# STM32G4_V1.net
KiCad netlist of a schematic drawn in Altium Designer
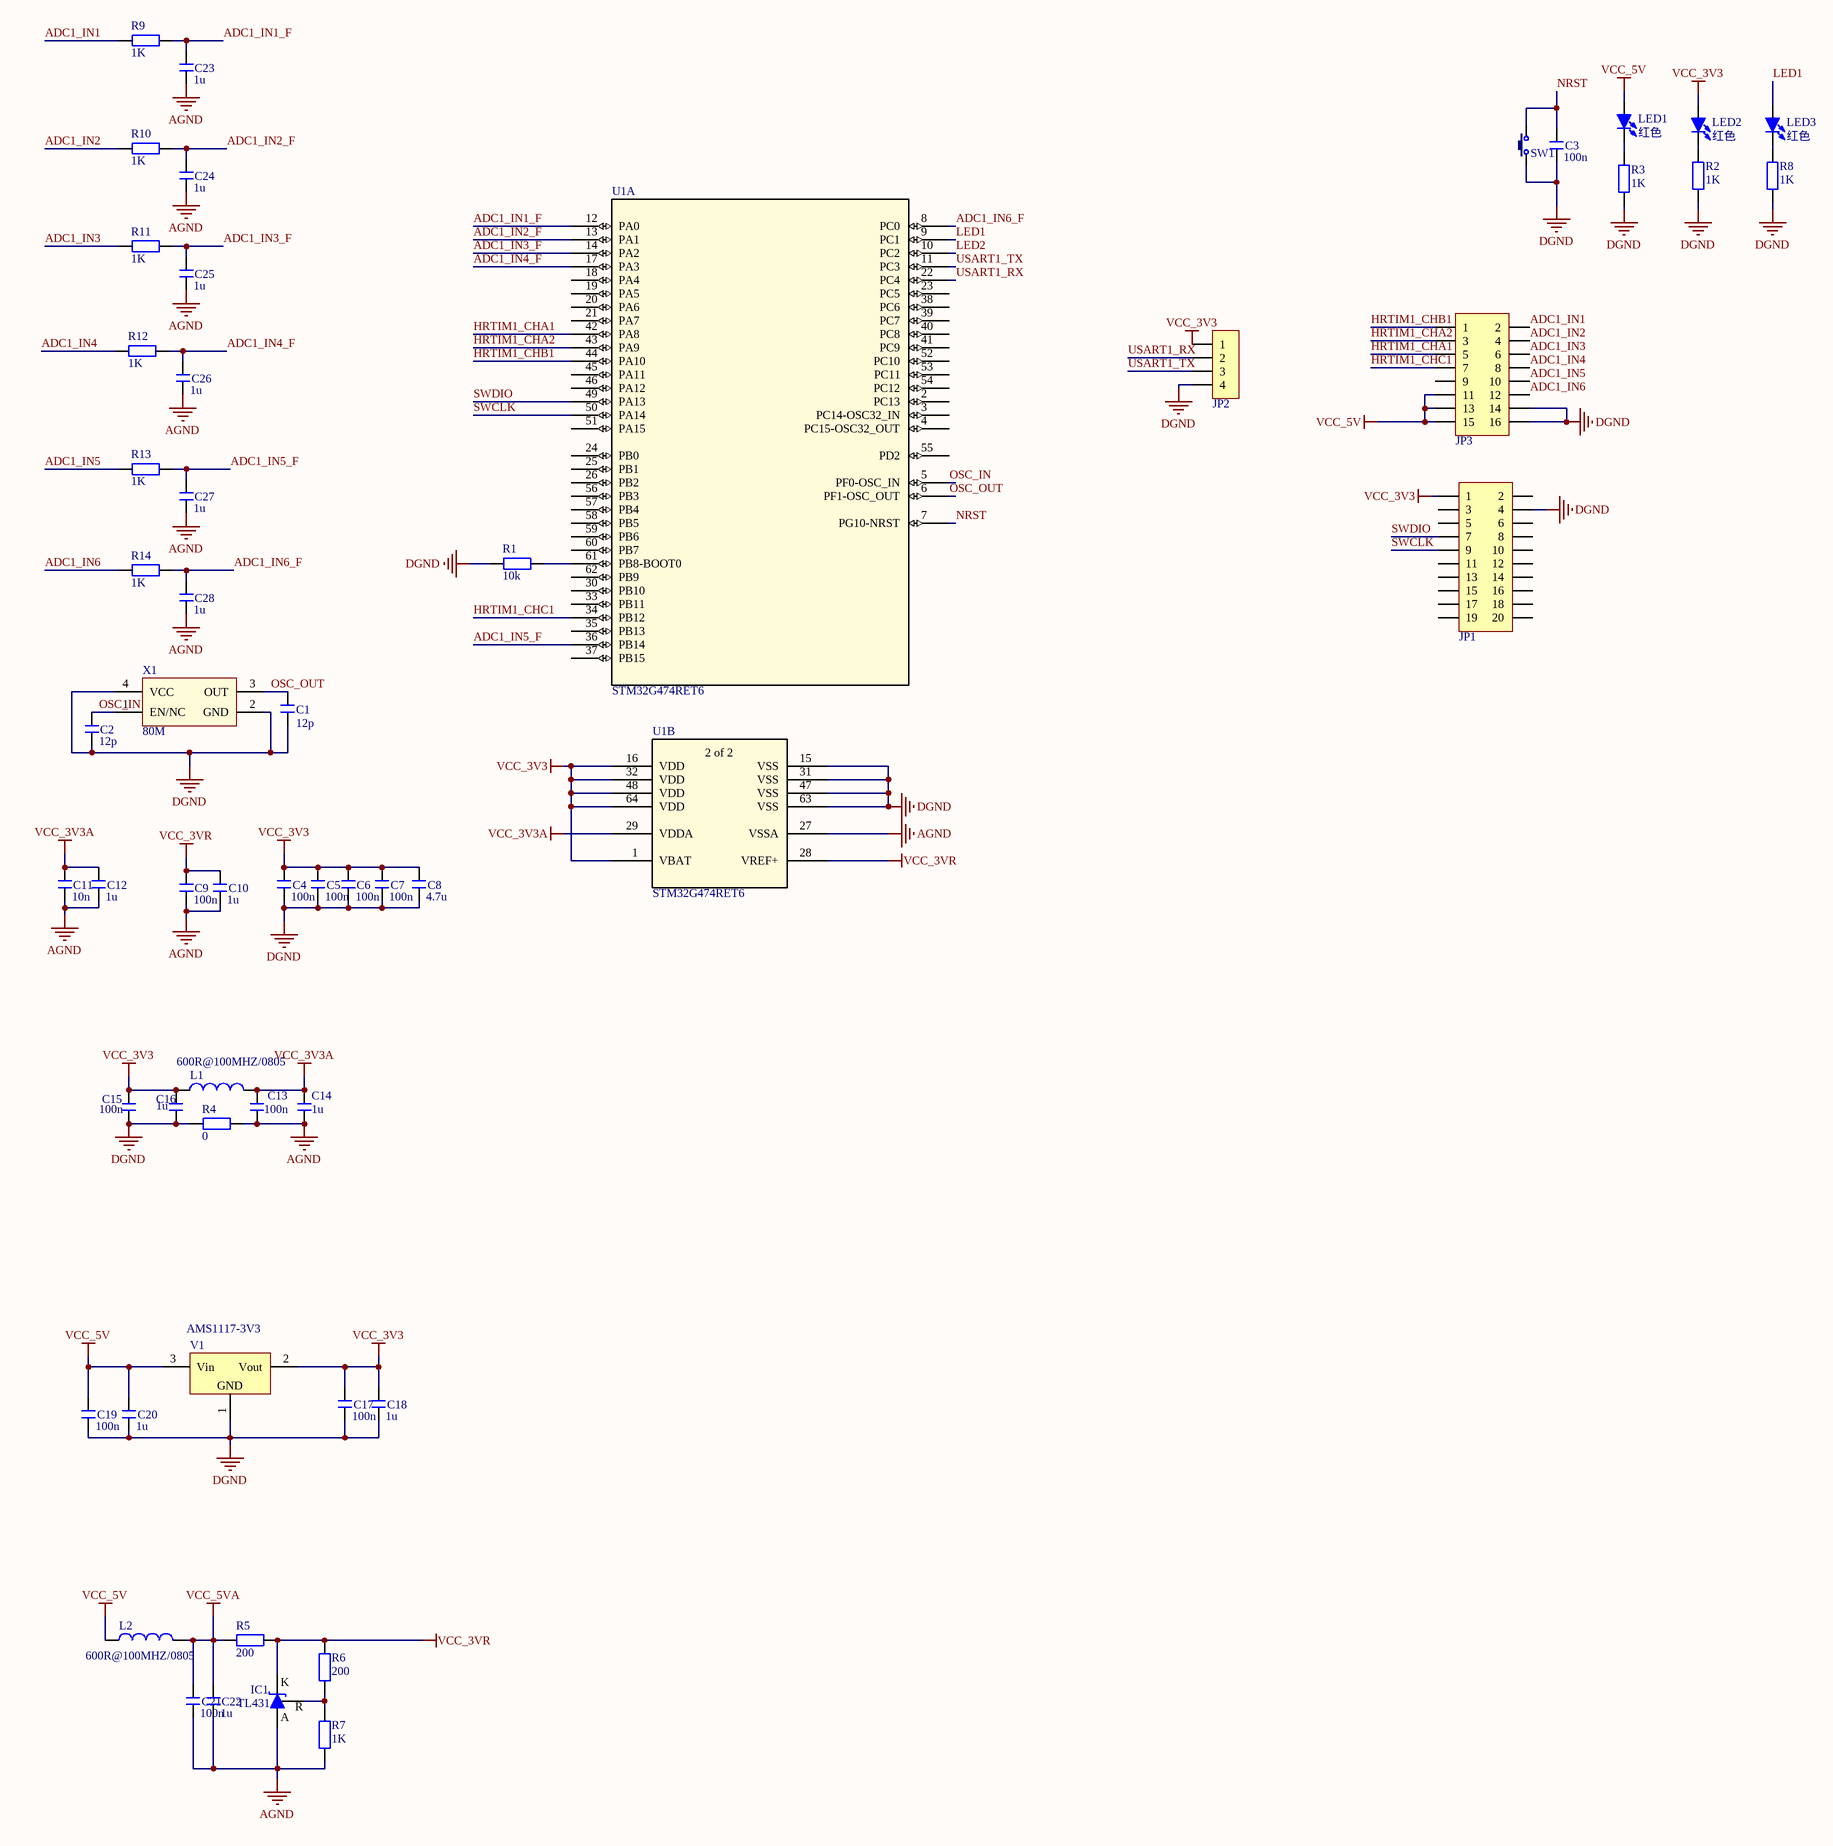
[diagram p0: STM32G4_V1.SchDoc]

(export (version "E")
  (design (tool "Eeschema 10.0.6"))
  (components
    (comp (ref "C1")
      (value "12p")
      (footprint "C 0603_L")
      (description "无极性贴片电容")
      (fields (field (name "版权归属") "源创客"))
      (libsource (lib "3.1   - 电阻-电容-电感") (part "C"))
    )
    (comp (ref "C2")
      (value "12p")
      (footprint "C 0603_L")
      (description "无极性贴片电容")
      (fields (field (name "版权归属") "源创客"))
      (libsource (lib "3.1   - 电阻-电容-电感") (part "C"))
    )
    (comp (ref "C3")
      (value "100n")
      (footprint "C 0603_L")
      (description "无极性贴片电容")
      (fields (field (name "版权归属") "源创客"))
      (libsource (lib "3.1   - 电阻-电容-电感") (part "C"))
    )
    (comp (ref "C4")
      (value "100n")
      (footprint "C 0603_L")
      (description "无极性贴片电容")
      (fields (field (name "版权归属") "源创客"))
      (libsource (lib "3.1   - 电阻-电容-电感") (part "C"))
    )
    (comp (ref "C5")
      (value "100n")
      (footprint "C 0603_L")
      (description "无极性贴片电容")
      (fields (field (name "版权归属") "源创客"))
      (libsource (lib "3.1   - 电阻-电容-电感") (part "C"))
    )
    (comp (ref "C6")
      (value "100n")
      (footprint "C 0603_L")
      (description "无极性贴片电容")
      (fields (field (name "版权归属") "源创客"))
      (libsource (lib "3.1   - 电阻-电容-电感") (part "C"))
    )
    (comp (ref "C7")
      (value "100n")
      (footprint "C 0603_L")
      (description "无极性贴片电容")
      (fields (field (name "版权归属") "源创客"))
      (libsource (lib "3.1   - 电阻-电容-电感") (part "C"))
    )
    (comp (ref "C8")
      (value "4.7u")
      (footprint "C 0603_L")
      (description "无极性贴片电容")
      (fields (field (name "版权归属") "源创客"))
      (libsource (lib "3.1   - 电阻-电容-电感") (part "C"))
    )
    (comp (ref "C9")
      (value "100n")
      (footprint "C 0603_L")
      (description "无极性贴片电容")
      (fields (field (name "版权归属") "源创客"))
      (libsource (lib "3.1   - 电阻-电容-电感") (part "C"))
    )
    (comp (ref "C10")
      (value "1u")
      (footprint "C 0603_L")
      (description "无极性贴片电容")
      (fields (field (name "版权归属") "源创客"))
      (libsource (lib "3.1   - 电阻-电容-电感") (part "C"))
    )
    (comp (ref "C11")
      (value "10n")
      (footprint "C 0603_L")
      (description "无极性贴片电容")
      (fields (field (name "版权归属") "源创客"))
      (libsource (lib "3.1   - 电阻-电容-电感") (part "C"))
    )
    (comp (ref "C12")
      (value "1u")
      (footprint "C 0603_L")
      (description "无极性贴片电容")
      (fields (field (name "版权归属") "源创客"))
      (libsource (lib "3.1   - 电阻-电容-电感") (part "C"))
    )
    (comp (ref "C13")
      (value "100n")
      (footprint "C 0603_L")
      (description "无极性贴片电容")
      (fields (field (name "版权归属") "源创客"))
      (libsource (lib "3.1   - 电阻-电容-电感") (part "C"))
    )
    (comp (ref "C14")
      (value "1u")
      (footprint "C 0603_L")
      (description "无极性贴片电容")
      (fields (field (name "版权归属") "源创客"))
      (libsource (lib "3.1   - 电阻-电容-电感") (part "C"))
    )
    (comp (ref "C15")
      (value "100n")
      (footprint "C 0603_L")
      (description "无极性贴片电容")
      (fields (field (name "版权归属") "源创客"))
      (libsource (lib "3.1   - 电阻-电容-电感") (part "C"))
    )
    (comp (ref "C16")
      (value "1u")
      (footprint "C 0603_L")
      (description "无极性贴片电容")
      (fields (field (name "版权归属") "源创客"))
      (libsource (lib "3.1   - 电阻-电容-电感") (part "C"))
    )
    (comp (ref "C17")
      (value "100n")
      (footprint "C 0603_L")
      (description "无极性贴片电容")
      (fields (field (name "版权归属") "源创客"))
      (libsource (lib "3.1   - 电阻-电容-电感") (part "C"))
    )
    (comp (ref "C18")
      (value "1u")
      (footprint "C 0603_L")
      (description "无极性贴片电容")
      (fields (field (name "版权归属") "源创客"))
      (libsource (lib "3.1   - 电阻-电容-电感") (part "C"))
    )
    (comp (ref "C19")
      (value "100n")
      (footprint "C 0603_L")
      (description "无极性贴片电容")
      (fields (field (name "版权归属") "源创客"))
      (libsource (lib "3.1   - 电阻-电容-电感") (part "C"))
    )
    (comp (ref "C20")
      (value "1u")
      (footprint "C 0603_L")
      (description "无极性贴片电容")
      (fields (field (name "版权归属") "源创客"))
      (libsource (lib "3.1   - 电阻-电容-电感") (part "C"))
    )
    (comp (ref "C21")
      (value "100n")
      (footprint "C 0603_L")
      (description "无极性贴片电容")
      (fields (field (name "版权归属") "源创客"))
      (libsource (lib "3.1   - 电阻-电容-电感") (part "C"))
    )
    (comp (ref "C22")
      (value "1u")
      (footprint "C 0603_L")
      (description "无极性贴片电容")
      (fields (field (name "版权归属") "源创客"))
      (libsource (lib "3.1   - 电阻-电容-电感") (part "C"))
    )
    (comp (ref "C23")
      (value "1u")
      (footprint "C 0603_L")
      (description "无极性贴片电容")
      (fields (field (name "版权归属") "源创客"))
      (libsource (lib "3.1   - 电阻-电容-电感") (part "C"))
    )
    (comp (ref "C24")
      (value "1u")
      (footprint "C 0603_L")
      (description "无极性贴片电容")
      (fields (field (name "版权归属") "源创客"))
      (libsource (lib "3.1   - 电阻-电容-电感") (part "C"))
    )
    (comp (ref "C25")
      (value "1u")
      (footprint "C 0603_L")
      (description "无极性贴片电容")
      (fields (field (name "版权归属") "源创客"))
      (libsource (lib "3.1   - 电阻-电容-电感") (part "C"))
    )
    (comp (ref "C26")
      (value "1u")
      (footprint "C 0603_L")
      (description "无极性贴片电容")
      (fields (field (name "版权归属") "源创客"))
      (libsource (lib "3.1   - 电阻-电容-电感") (part "C"))
    )
    (comp (ref "C27")
      (value "1u")
      (footprint "C 0603_L")
      (description "无极性贴片电容")
      (fields (field (name "版权归属") "源创客"))
      (libsource (lib "3.1   - 电阻-电容-电感") (part "C"))
    )
    (comp (ref "C28")
      (value "1u")
      (footprint "C 0603_L")
      (description "无极性贴片电容")
      (fields (field (name "版权归属") "源创客"))
      (libsource (lib "3.1   - 电阻-电容-电感") (part "C"))
    )
    (comp (ref "IC1")
      (value "TL431")
      (footprint "SOT23-3N")
      (description "可调基准稳压芯片")
      (fields (field (name "版权归属") "源创客"))
      (libsource (lib "1.3   - 电源类芯片") (part "TL431_SMD"))
    )
    (comp (ref "JP1")
      (value "Header 2X10")
      (footprint "IDC2.54-LI-2x10P")
      (description "10*2P接插件")
      (fields (field (name "版权归属") "源创客"))
      (libsource (lib "4.6   - 接插件-脚距2.54") (part "Header 10X2"))
    )
    (comp (ref "JP2")
      (value "HDR-1X4")
      (footprint "XH2.54-LI-4P")
      (description "4P接插件")
      (fields (field (name "版权归属") "源创客"))
      (libsource (lib "4.6   - 接插件-脚距2.54") (part "Header 4"))
    )
    (comp (ref "JP3")
      (value "Header 8X2")
      (footprint "HDR2.54-LI-2x8P")
      (description "8*2P接插件")
      (fields (field (name "版权归属") "源创客"))
      (libsource (lib "4.6   - 接插件-脚距2.54") (part "Header 8X2"))
    )
    (comp (ref "L1")
      (value "600R@100MHZ/0805")
      (footprint "L 0805_L")
      (description "小功率贴片电感")
      (fields (field (name "版权归属") "源创客"))
      (libsource (lib "3.1   - 电阻-电容-电感") (part "L"))
    )
    (comp (ref "L2")
      (value "600R@100MHZ/0805")
      (footprint "L 0805_L")
      (description "小功率贴片电感")
      (fields (field (name "版权归属") "源创客"))
      (libsource (lib "3.1   - 电阻-电容-电感") (part "L"))
    )
    (comp (ref "LED1")
      (value "红色")
      (footprint "LED 0805G")
      (description "贴片LED")
      (fields (field (name "版权归属") "源创客"))
      (libsource (lib "9.1   - LED") (part "LED-SMD"))
    )
    (comp (ref "LED2")
      (value "红色")
      (footprint "LED 0805G")
      (description "贴片LED")
      (fields (field (name "版权归属") "源创客"))
      (libsource (lib "9.1   - LED") (part "LED-SMD"))
    )
    (comp (ref "LED3")
      (value "红色")
      (footprint "LED 0805G")
      (description "贴片LED")
      (fields (field (name "版权归属") "源创客"))
      (libsource (lib "9.1   - LED") (part "LED-SMD"))
    )
    (comp (ref "R1")
      (value "10k")
      (footprint "R 0603_L")
      (description "贴片电阻")
      (fields (field (name "版权归属") "源创客"))
      (libsource (lib "3.1   - 电阻-电容-电感") (part "R"))
    )
    (comp (ref "R2")
      (value "1K")
      (footprint "R 0603_L")
      (description "贴片电阻")
      (fields (field (name "版权归属") "源创客"))
      (libsource (lib "3.1   - 电阻-电容-电感") (part "R"))
    )
    (comp (ref "R3")
      (value "1K")
      (footprint "R 0603_L")
      (description "贴片电阻")
      (fields (field (name "版权归属") "源创客"))
      (libsource (lib "3.1   - 电阻-电容-电感") (part "R"))
    )
    (comp (ref "R4")
      (value "0")
      (footprint "R 0603_L")
      (description "贴片电阻")
      (fields (field (name "版权归属") "源创客"))
      (libsource (lib "3.1   - 电阻-电容-电感") (part "R"))
    )
    (comp (ref "R5")
      (value "200")
      (footprint "R 0603_L")
      (description "贴片电阻")
      (fields (field (name "版权归属") "源创客"))
      (libsource (lib "3.1   - 电阻-电容-电感") (part "R"))
    )
    (comp (ref "R6")
      (value "200")
      (footprint "R 0603_L")
      (description "贴片电阻")
      (fields (field (name "版权归属") "源创客"))
      (libsource (lib "3.1   - 电阻-电容-电感") (part "R"))
    )
    (comp (ref "R7")
      (value "1K")
      (footprint "R 0603_L")
      (description "贴片电阻")
      (fields (field (name "版权归属") "源创客"))
      (libsource (lib "3.1   - 电阻-电容-电感") (part "R"))
    )
    (comp (ref "R8")
      (value "1K")
      (footprint "R 0603_L")
      (description "贴片电阻")
      (fields (field (name "版权归属") "源创客"))
      (libsource (lib "3.1   - 电阻-电容-电感") (part "R"))
    )
    (comp (ref "R9")
      (value "1K")
      (footprint "R 0603_L")
      (description "贴片电阻")
      (fields (field (name "版权归属") "源创客"))
      (libsource (lib "3.1   - 电阻-电容-电感") (part "R"))
    )
    (comp (ref "R10")
      (value "1K")
      (footprint "R 0603_L")
      (description "贴片电阻")
      (fields (field (name "版权归属") "源创客"))
      (libsource (lib "3.1   - 电阻-电容-电感") (part "R"))
    )
    (comp (ref "R11")
      (value "1K")
      (footprint "R 0603_L")
      (description "贴片电阻")
      (fields (field (name "版权归属") "源创客"))
      (libsource (lib "3.1   - 电阻-电容-电感") (part "R"))
    )
    (comp (ref "R12")
      (value "1K")
      (footprint "R 0603_L")
      (description "贴片电阻")
      (fields (field (name "版权归属") "源创客"))
      (libsource (lib "3.1   - 电阻-电容-电感") (part "R"))
    )
    (comp (ref "R13")
      (value "1K")
      (footprint "R 0603_L")
      (description "贴片电阻")
      (fields (field (name "版权归属") "源创客"))
      (libsource (lib "3.1   - 电阻-电容-电感") (part "R"))
    )
    (comp (ref "R14")
      (value "1K")
      (footprint "R 0603_L")
      (description "贴片电阻")
      (fields (field (name "版权归属") "源创客"))
      (libsource (lib "3.1   - 电阻-电容-电感") (part "R"))
    )
    (comp (ref "SW1")
      (value "3x6x5")
      (footprint "TSW SMD-3*6*2.5")
      (description "3x6轻触开关")
      (fields (field (name "版权归属") "源创客"))
      (libsource (lib "5.1   - 按键-开关") (part "TSW 3x6"))
    )
    (comp (ref "U1")
      (value "STM32G474RET6")
      (footprint "LQFP64-10x10mm")
      (description "No Description Available")
      (libsource (lib "STM32G474RET6") (part "STM32G474RET6"))
    )
    (comp (ref "V1")
      (value "AMS1117-3V3")
      (footprint "SOT223_L")
      (description "三端稳压芯片")
      (fields (field (name "版权归属") "源创客"))
      (libsource (lib "1.3   - 电源类芯片") (part "AMS1117"))
    )
    (comp (ref "X1")
      (value "80M")
      (footprint "OSC 3225-4P")
      (description "4脚有源晶振")
      (fields (field (name "版权归属") "源创客"))
      (libsource (lib "10.1 - 保险丝-晶振") (part "XTAL-ACT-4P"))
    )
  )
  (nets
    (net (code "1") (name "/ADC1_IN1") (class "Default")
      (node (ref "JP3") (pin "2") (pinfunction "2_2") (pintype "passive"))
      (node (ref "R9") (pin "2") (pinfunction "2_2") (pintype "passive"))
    )
    (net (code "2") (name "/ADC1_IN1_F") (class "Default")
      (node (ref "C23") (pin "1") (pinfunction "1_1") (pintype "passive"))
      (node (ref "R9") (pin "1") (pinfunction "1_1") (pintype "passive"))
      (node (ref "U1") (pin "12") (pinfunction "PA0_12") (pintype "bidirectional"))
    )
    (net (code "3") (name "/ADC1_IN2") (class "Default")
      (node (ref "JP3") (pin "4") (pinfunction "4_4") (pintype "passive"))
      (node (ref "R10") (pin "2") (pinfunction "2_2") (pintype "passive"))
    )
    (net (code "4") (name "/ADC1_IN2_F") (class "Default")
      (node (ref "C24") (pin "1") (pinfunction "1_1") (pintype "passive"))
      (node (ref "R10") (pin "1") (pinfunction "1_1") (pintype "passive"))
      (node (ref "U1") (pin "13") (pinfunction "PA1_13") (pintype "bidirectional"))
    )
    (net (code "5") (name "/ADC1_IN3") (class "Default")
      (node (ref "JP3") (pin "6") (pinfunction "6_6") (pintype "passive"))
      (node (ref "R11") (pin "2") (pinfunction "2_2") (pintype "passive"))
    )
    (net (code "6") (name "/ADC1_IN3_F") (class "Default")
      (node (ref "C25") (pin "1") (pinfunction "1_1") (pintype "passive"))
      (node (ref "R11") (pin "1") (pinfunction "1_1") (pintype "passive"))
      (node (ref "U1") (pin "14") (pinfunction "PA2_14") (pintype "bidirectional"))
    )
    (net (code "7") (name "/ADC1_IN4") (class "Default")
      (node (ref "JP3") (pin "8") (pinfunction "8_8") (pintype "passive"))
      (node (ref "R12") (pin "2") (pinfunction "2_2") (pintype "passive"))
    )
    (net (code "8") (name "/ADC1_IN4_F") (class "Default")
      (node (ref "C26") (pin "1") (pinfunction "1_1") (pintype "passive"))
      (node (ref "R12") (pin "1") (pinfunction "1_1") (pintype "passive"))
      (node (ref "U1") (pin "17") (pinfunction "PA3_17") (pintype "bidirectional"))
    )
    (net (code "9") (name "/ADC1_IN5") (class "Default")
      (node (ref "JP3") (pin "10") (pinfunction "10_10") (pintype "passive"))
      (node (ref "R13") (pin "2") (pinfunction "2_2") (pintype "passive"))
    )
    (net (code "10") (name "/ADC1_IN5_F") (class "Default")
      (node (ref "C27") (pin "1") (pinfunction "1_1") (pintype "passive"))
      (node (ref "R13") (pin "1") (pinfunction "1_1") (pintype "passive"))
      (node (ref "U1") (pin "36") (pinfunction "PB14_36") (pintype "bidirectional"))
    )
    (net (code "11") (name "/ADC1_IN6") (class "Default")
      (node (ref "JP3") (pin "12") (pinfunction "12_12") (pintype "passive"))
      (node (ref "R14") (pin "2") (pinfunction "2_2") (pintype "passive"))
    )
    (net (code "12") (name "/ADC1_IN6_F") (class "Default")
      (node (ref "C28") (pin "1") (pinfunction "1_1") (pintype "passive"))
      (node (ref "R14") (pin "1") (pinfunction "1_1") (pintype "passive"))
      (node (ref "U1") (pin "8") (pinfunction "PC0_8") (pintype "bidirectional"))
    )
    (net (code "13") (name "/HRTIM1_CHA1") (class "Default")
      (node (ref "JP3") (pin "5") (pinfunction "5_5") (pintype "passive"))
      (node (ref "U1") (pin "42") (pinfunction "PA8_42") (pintype "bidirectional"))
    )
    (net (code "14") (name "/HRTIM1_CHA2") (class "Default")
      (node (ref "JP3") (pin "3") (pinfunction "3_3") (pintype "passive"))
      (node (ref "U1") (pin "43") (pinfunction "PA9_43") (pintype "bidirectional"))
    )
    (net (code "15") (name "/HRTIM1_CHB1") (class "Default")
      (node (ref "JP3") (pin "1") (pinfunction "1_1") (pintype "passive"))
      (node (ref "U1") (pin "44") (pinfunction "PA10_44") (pintype "bidirectional"))
    )
    (net (code "16") (name "/HRTIM1_CHC1") (class "Default")
      (node (ref "JP3") (pin "7") (pinfunction "7_7") (pintype "passive"))
      (node (ref "U1") (pin "34") (pinfunction "PB12_34") (pintype "bidirectional"))
    )
    (net (code "17") (name "/LED1") (class "Default")
      (node (ref "LED3") (pin "1") (pinfunction "A_1") (pintype "passive"))
      (node (ref "U1") (pin "9") (pinfunction "PC1_9") (pintype "bidirectional"))
    )
    (net (code "18") (name "/LED2") (class "Default")
      (node (ref "U1") (pin "10") (pinfunction "PC2_10") (pintype "bidirectional"))
    )
    (net (code "19") (name "/NRST") (class "Default")
      (node (ref "C3") (pin "1") (pinfunction "1_1") (pintype "passive"))
      (node (ref "SW1") (pin "2") (pinfunction "2_2") (pintype "passive"))
      (node (ref "U1") (pin "7") (pinfunction "PG10-NRST_7") (pintype "bidirectional"))
    )
    (net (code "20") (name "/OSC_IN") (class "Default")
      (node (ref "C2") (pin "1") (pinfunction "1_1") (pintype "passive"))
      (node (ref "U1") (pin "5") (pinfunction "PF0-OSC_IN_5") (pintype "bidirectional"))
      (node (ref "X1") (pin "1") (pinfunction "EN/NC_1") (pintype "passive"))
    )
    (net (code "21") (name "/OSC_OUT") (class "Default")
      (node (ref "C1") (pin "2") (pinfunction "2_2") (pintype "passive"))
      (node (ref "U1") (pin "6") (pinfunction "PF1-OSC_OUT_6") (pintype "bidirectional"))
      (node (ref "X1") (pin "3") (pinfunction "OUT_3") (pintype "passive"))
    )
    (net (code "22") (name "/SWCLK") (class "Default")
      (node (ref "JP1") (pin "9") (pinfunction "9_9") (pintype "passive"))
      (node (ref "U1") (pin "50") (pinfunction "PA14_50") (pintype "bidirectional"))
    )
    (net (code "23") (name "/SWDIO") (class "Default")
      (node (ref "JP1") (pin "7") (pinfunction "7_7") (pintype "passive"))
      (node (ref "U1") (pin "49") (pinfunction "PA13_49") (pintype "bidirectional"))
    )
    (net (code "24") (name "/USART1_RX") (class "Default")
      (node (ref "JP2") (pin "2") (pinfunction "2_2") (pintype "passive"))
      (node (ref "U1") (pin "22") (pinfunction "PC4_22") (pintype "bidirectional"))
    )
    (net (code "25") (name "/USART1_TX") (class "Default")
      (node (ref "JP2") (pin "3") (pinfunction "3_3") (pintype "passive"))
      (node (ref "U1") (pin "11") (pinfunction "PC3_11") (pintype "bidirectional"))
    )
    (net (code "26") (name "AGND") (class "Default")
      (node (ref "C10") (pin "2") (pinfunction "2_2") (pintype "passive"))
      (node (ref "C11") (pin "2") (pinfunction "2_2") (pintype "passive"))
      (node (ref "C12") (pin "2") (pinfunction "2_2") (pintype "passive"))
      (node (ref "C13") (pin "2") (pinfunction "2_2") (pintype "passive"))
      (node (ref "C14") (pin "2") (pinfunction "2_2") (pintype "passive"))
      (node (ref "C21") (pin "2") (pinfunction "2_2") (pintype "passive"))
      (node (ref "C22") (pin "2") (pinfunction "2_2") (pintype "passive"))
      (node (ref "C23") (pin "2") (pinfunction "2_2") (pintype "passive"))
      (node (ref "C24") (pin "2") (pinfunction "2_2") (pintype "passive"))
      (node (ref "C25") (pin "2") (pinfunction "2_2") (pintype "passive"))
      (node (ref "C26") (pin "2") (pinfunction "2_2") (pintype "passive"))
      (node (ref "C27") (pin "2") (pinfunction "2_2") (pintype "passive"))
      (node (ref "C28") (pin "2") (pinfunction "2_2") (pintype "passive"))
      (node (ref "C9") (pin "2") (pinfunction "2_2") (pintype "passive"))
      (node (ref "IC1") (pin "3") (pinfunction "A_3") (pintype "passive"))
      (node (ref "R4") (pin "1") (pinfunction "1_1") (pintype "passive"))
      (node (ref "R7") (pin "1") (pinfunction "1_1") (pintype "passive"))
      (node (ref "U1") (pin "27") (pinfunction "VSSA_27") (pintype "power_in"))
    )
    (net (code "27") (name "DGND") (class "Default")
      (node (ref "C1") (pin "1") (pinfunction "1_1") (pintype "passive"))
      (node (ref "C15") (pin "2") (pinfunction "2_2") (pintype "passive"))
      (node (ref "C16") (pin "2") (pinfunction "2_2") (pintype "passive"))
      (node (ref "C17") (pin "2") (pinfunction "2_2") (pintype "passive"))
      (node (ref "C18") (pin "2") (pinfunction "2_2") (pintype "passive"))
      (node (ref "C19") (pin "2") (pinfunction "2_2") (pintype "passive"))
      (node (ref "C2") (pin "2") (pinfunction "2_2") (pintype "passive"))
      (node (ref "C20") (pin "2") (pinfunction "2_2") (pintype "passive"))
      (node (ref "C3") (pin "2") (pinfunction "2_2") (pintype "passive"))
      (node (ref "C4") (pin "2") (pinfunction "2_2") (pintype "passive"))
      (node (ref "C5") (pin "2") (pinfunction "2_2") (pintype "passive"))
      (node (ref "C6") (pin "2") (pinfunction "2_2") (pintype "passive"))
      (node (ref "C7") (pin "2") (pinfunction "2_2") (pintype "passive"))
      (node (ref "C8") (pin "2") (pinfunction "2_2") (pintype "passive"))
      (node (ref "JP1") (pin "4") (pinfunction "4_4") (pintype "passive"))
      (node (ref "JP2") (pin "4") (pinfunction "4_4") (pintype "passive"))
      (node (ref "JP3") (pin "14") (pinfunction "14_14") (pintype "passive"))
      (node (ref "JP3") (pin "16") (pinfunction "16_16") (pintype "passive"))
      (node (ref "R1") (pin "2") (pinfunction "2_2") (pintype "passive"))
      (node (ref "R2") (pin "1") (pinfunction "1_1") (pintype "passive"))
      (node (ref "R3") (pin "1") (pinfunction "1_1") (pintype "passive"))
      (node (ref "R4") (pin "2") (pinfunction "2_2") (pintype "passive"))
      (node (ref "R8") (pin "1") (pinfunction "1_1") (pintype "passive"))
      (node (ref "SW1") (pin "1") (pinfunction "1_1") (pintype "passive"))
      (node (ref "U1") (pin "15") (pinfunction "VSS_15") (pintype "power_in"))
      (node (ref "U1") (pin "31") (pinfunction "VSS_31") (pintype "power_in"))
      (node (ref "U1") (pin "47") (pinfunction "VSS_47") (pintype "power_in"))
      (node (ref "U1") (pin "63") (pinfunction "VSS_63") (pintype "power_in"))
      (node (ref "V1") (pin "1") (pinfunction "GND_1") (pintype "passive"))
      (node (ref "X1") (pin "2") (pinfunction "GND_2") (pintype "passive"))
      (node (ref "X1") (pin "4") (pinfunction "VCC_4") (pintype "passive"))
    )
    (net (code "28") (name "Net-(IC1-R)") (class "Default")
      (node (ref "IC1") (pin "2") (pinfunction "R_2") (pintype "passive"))
      (node (ref "R6") (pin "1") (pinfunction "1_1") (pintype "passive"))
      (node (ref "R7") (pin "2") (pinfunction "2_2") (pintype "passive"))
    )
    (net (code "29") (name "Net-(LED1-K)") (class "Default")
      (node (ref "LED1") (pin "2") (pinfunction "K_2") (pintype "passive"))
      (node (ref "R3") (pin "2") (pinfunction "2_2") (pintype "passive"))
    )
    (net (code "30") (name "Net-(LED2-K)") (class "Default")
      (node (ref "LED2") (pin "2") (pinfunction "K_2") (pintype "passive"))
      (node (ref "R2") (pin "2") (pinfunction "2_2") (pintype "passive"))
    )
    (net (code "31") (name "Net-(LED3-K)") (class "Default")
      (node (ref "LED3") (pin "2") (pinfunction "K_2") (pintype "passive"))
      (node (ref "R8") (pin "2") (pinfunction "2_2") (pintype "passive"))
    )
    (net (code "32") (name "Net-(U1A-PB8-BOOT0)") (class "Default")
      (node (ref "R1") (pin "1") (pinfunction "1_1") (pintype "passive"))
      (node (ref "U1") (pin "61") (pinfunction "PB8-BOOT0_61") (pintype "bidirectional"))
    )
    (net (code "33") (name "VCC_3V3") (class "Default")
      (node (ref "C15") (pin "1") (pinfunction "1_1") (pintype "passive"))
      (node (ref "C16") (pin "1") (pinfunction "1_1") (pintype "passive"))
      (node (ref "C17") (pin "1") (pinfunction "1_1") (pintype "passive"))
      (node (ref "C18") (pin "1") (pinfunction "1_1") (pintype "passive"))
      (node (ref "C4") (pin "1") (pinfunction "1_1") (pintype "passive"))
      (node (ref "C5") (pin "1") (pinfunction "1_1") (pintype "passive"))
      (node (ref "C6") (pin "1") (pinfunction "1_1") (pintype "passive"))
      (node (ref "C7") (pin "1") (pinfunction "1_1") (pintype "passive"))
      (node (ref "C8") (pin "1") (pinfunction "1_1") (pintype "passive"))
      (node (ref "JP1") (pin "1") (pinfunction "1_1") (pintype "passive"))
      (node (ref "JP2") (pin "1") (pinfunction "1_1") (pintype "passive"))
      (node (ref "L1") (pin "1") (pinfunction "1_1") (pintype "passive"))
      (node (ref "LED2") (pin "1") (pinfunction "A_1") (pintype "passive"))
      (node (ref "U1") (pin "1") (pinfunction "VBAT_1") (pintype "power_in"))
      (node (ref "U1") (pin "16") (pinfunction "VDD_16") (pintype "power_in"))
      (node (ref "U1") (pin "32") (pinfunction "VDD_32") (pintype "power_in"))
      (node (ref "U1") (pin "48") (pinfunction "VDD_48") (pintype "power_in"))
      (node (ref "U1") (pin "64") (pinfunction "VDD_64") (pintype "power_in"))
      (node (ref "V1") (pin "2") (pinfunction "Vout_2") (pintype "passive"))
    )
    (net (code "34") (name "VCC_3V3A") (class "Default")
      (node (ref "C11") (pin "1") (pinfunction "1_1") (pintype "passive"))
      (node (ref "C12") (pin "1") (pinfunction "1_1") (pintype "passive"))
      (node (ref "C13") (pin "1") (pinfunction "1_1") (pintype "passive"))
      (node (ref "C14") (pin "1") (pinfunction "1_1") (pintype "passive"))
      (node (ref "L1") (pin "2") (pinfunction "2_2") (pintype "passive"))
      (node (ref "U1") (pin "29") (pinfunction "VDDA_29") (pintype "power_in"))
    )
    (net (code "35") (name "VCC_3VR") (class "Default")
      (node (ref "C10") (pin "1") (pinfunction "1_1") (pintype "passive"))
      (node (ref "C9") (pin "1") (pinfunction "1_1") (pintype "passive"))
      (node (ref "IC1") (pin "1") (pinfunction "K_1") (pintype "passive"))
      (node (ref "R5") (pin "1") (pinfunction "1_1") (pintype "passive"))
      (node (ref "R6") (pin "2") (pinfunction "2_2") (pintype "passive"))
      (node (ref "U1") (pin "28") (pinfunction "VREF+_28") (pintype "power_in"))
    )
    (net (code "36") (name "VCC_5V") (class "Default")
      (node (ref "C19") (pin "1") (pinfunction "1_1") (pintype "passive"))
      (node (ref "C20") (pin "1") (pinfunction "1_1") (pintype "passive"))
      (node (ref "JP3") (pin "11") (pinfunction "11_11") (pintype "passive"))
      (node (ref "JP3") (pin "13") (pinfunction "13_13") (pintype "passive"))
      (node (ref "JP3") (pin "15") (pinfunction "15_15") (pintype "passive"))
      (node (ref "L2") (pin "1") (pinfunction "1_1") (pintype "passive"))
      (node (ref "LED1") (pin "1") (pinfunction "A_1") (pintype "passive"))
      (node (ref "V1") (pin "3") (pinfunction "Vin_3") (pintype "passive"))
    )
    (net (code "37") (name "VCC_5VA") (class "Default")
      (node (ref "C21") (pin "1") (pinfunction "1_1") (pintype "passive"))
      (node (ref "C22") (pin "1") (pinfunction "1_1") (pintype "passive"))
      (node (ref "L2") (pin "2") (pinfunction "2_2") (pintype "passive"))
      (node (ref "R5") (pin "2") (pinfunction "2_2") (pintype "passive"))
    )
    (net (code "38") (name "unconnected-(JP1-Pad2)") (class "Default")
      (node (ref "JP1") (pin "2") (pinfunction "2_2") (pintype "passive"))
    )
    (net (code "39") (name "unconnected-(JP1-Pad3)") (class "Default")
      (node (ref "JP1") (pin "3") (pinfunction "3_3") (pintype "passive"))
    )
    (net (code "40") (name "unconnected-(JP1-Pad5)") (class "Default")
      (node (ref "JP1") (pin "5") (pinfunction "5_5") (pintype "passive"))
    )
    (net (code "41") (name "unconnected-(JP1-Pad6)") (class "Default")
      (node (ref "JP1") (pin "6") (pinfunction "6_6") (pintype "passive"))
    )
    (net (code "42") (name "unconnected-(JP1-Pad8)") (class "Default")
      (node (ref "JP1") (pin "8") (pinfunction "8_8") (pintype "passive"))
    )
    (net (code "43") (name "unconnected-(JP1-Pad10)") (class "Default")
      (node (ref "JP1") (pin "10") (pinfunction "10_10") (pintype "passive"))
    )
    (net (code "44") (name "unconnected-(JP1-Pad11)") (class "Default")
      (node (ref "JP1") (pin "11") (pinfunction "11_11") (pintype "passive"))
    )
    (net (code "45") (name "unconnected-(JP1-Pad12)") (class "Default")
      (node (ref "JP1") (pin "12") (pinfunction "12_12") (pintype "passive"))
    )
    (net (code "46") (name "unconnected-(JP1-Pad13)") (class "Default")
      (node (ref "JP1") (pin "13") (pinfunction "13_13") (pintype "passive"))
    )
    (net (code "47") (name "unconnected-(JP1-Pad14)") (class "Default")
      (node (ref "JP1") (pin "14") (pinfunction "14_14") (pintype "passive"))
    )
    (net (code "48") (name "unconnected-(JP1-Pad15)") (class "Default")
      (node (ref "JP1") (pin "15") (pinfunction "15_15") (pintype "passive"))
    )
    (net (code "49") (name "unconnected-(JP1-Pad16)") (class "Default")
      (node (ref "JP1") (pin "16") (pinfunction "16_16") (pintype "passive"))
    )
    (net (code "50") (name "unconnected-(JP1-Pad17)") (class "Default")
      (node (ref "JP1") (pin "17") (pinfunction "17_17") (pintype "passive"))
    )
    (net (code "51") (name "unconnected-(JP1-Pad18)") (class "Default")
      (node (ref "JP1") (pin "18") (pinfunction "18_18") (pintype "passive"))
    )
    (net (code "52") (name "unconnected-(JP1-Pad19)") (class "Default")
      (node (ref "JP1") (pin "19") (pinfunction "19_19") (pintype "passive"))
    )
    (net (code "53") (name "unconnected-(JP1-Pad20)") (class "Default")
      (node (ref "JP1") (pin "20") (pinfunction "20_20") (pintype "passive"))
    )
    (net (code "54") (name "unconnected-(JP3-Pad9)") (class "Default")
      (node (ref "JP3") (pin "9") (pinfunction "9_9") (pintype "passive"))
    )
    (net (code "55") (name "unconnected-(U1A-PA4-Pad18)") (class "Default")
      (node (ref "U1") (pin "18") (pinfunction "PA4_18") (pintype "bidirectional"))
    )
    (net (code "56") (name "unconnected-(U1A-PA5-Pad19)") (class "Default")
      (node (ref "U1") (pin "19") (pinfunction "PA5_19") (pintype "bidirectional"))
    )
    (net (code "57") (name "unconnected-(U1A-PA6-Pad20)") (class "Default")
      (node (ref "U1") (pin "20") (pinfunction "PA6_20") (pintype "bidirectional"))
    )
    (net (code "58") (name "unconnected-(U1A-PA7-Pad21)") (class "Default")
      (node (ref "U1") (pin "21") (pinfunction "PA7_21") (pintype "bidirectional"))
    )
    (net (code "59") (name "unconnected-(U1A-PA11-Pad45)") (class "Default")
      (node (ref "U1") (pin "45") (pinfunction "PA11_45") (pintype "bidirectional"))
    )
    (net (code "60") (name "unconnected-(U1A-PA12-Pad46)") (class "Default")
      (node (ref "U1") (pin "46") (pinfunction "PA12_46") (pintype "bidirectional"))
    )
    (net (code "61") (name "unconnected-(U1A-PA15-Pad51)") (class "Default")
      (node (ref "U1") (pin "51") (pinfunction "PA15_51") (pintype "bidirectional"))
    )
    (net (code "62") (name "unconnected-(U1A-PB0-Pad24)") (class "Default")
      (node (ref "U1") (pin "24") (pinfunction "PB0_24") (pintype "bidirectional"))
    )
    (net (code "63") (name "unconnected-(U1A-PB1-Pad25)") (class "Default")
      (node (ref "U1") (pin "25") (pinfunction "PB1_25") (pintype "bidirectional"))
    )
    (net (code "64") (name "unconnected-(U1A-PB2-Pad26)") (class "Default")
      (node (ref "U1") (pin "26") (pinfunction "PB2_26") (pintype "bidirectional"))
    )
    (net (code "65") (name "unconnected-(U1A-PB3-Pad56)") (class "Default")
      (node (ref "U1") (pin "56") (pinfunction "PB3_56") (pintype "bidirectional"))
    )
    (net (code "66") (name "unconnected-(U1A-PB4-Pad57)") (class "Default")
      (node (ref "U1") (pin "57") (pinfunction "PB4_57") (pintype "bidirectional"))
    )
    (net (code "67") (name "unconnected-(U1A-PB5-Pad58)") (class "Default")
      (node (ref "U1") (pin "58") (pinfunction "PB5_58") (pintype "bidirectional"))
    )
    (net (code "68") (name "unconnected-(U1A-PB6-Pad59)") (class "Default")
      (node (ref "U1") (pin "59") (pinfunction "PB6_59") (pintype "bidirectional"))
    )
    (net (code "69") (name "unconnected-(U1A-PB7-Pad60)") (class "Default")
      (node (ref "U1") (pin "60") (pinfunction "PB7_60") (pintype "bidirectional"))
    )
    (net (code "70") (name "unconnected-(U1A-PB9-Pad62)") (class "Default")
      (node (ref "U1") (pin "62") (pinfunction "PB9_62") (pintype "bidirectional"))
    )
    (net (code "71") (name "unconnected-(U1A-PB10-Pad30)") (class "Default")
      (node (ref "U1") (pin "30") (pinfunction "PB10_30") (pintype "bidirectional"))
    )
    (net (code "72") (name "unconnected-(U1A-PB11-Pad33)") (class "Default")
      (node (ref "U1") (pin "33") (pinfunction "PB11_33") (pintype "bidirectional"))
    )
    (net (code "73") (name "unconnected-(U1A-PB13-Pad35)") (class "Default")
      (node (ref "U1") (pin "35") (pinfunction "PB13_35") (pintype "bidirectional"))
    )
    (net (code "74") (name "unconnected-(U1A-PB15-Pad37)") (class "Default")
      (node (ref "U1") (pin "37") (pinfunction "PB15_37") (pintype "bidirectional"))
    )
    (net (code "75") (name "unconnected-(U1A-PC5-Pad23)") (class "Default")
      (node (ref "U1") (pin "23") (pinfunction "PC5_23") (pintype "bidirectional"))
    )
    (net (code "76") (name "unconnected-(U1A-PC6-Pad38)") (class "Default")
      (node (ref "U1") (pin "38") (pinfunction "PC6_38") (pintype "bidirectional"))
    )
    (net (code "77") (name "unconnected-(U1A-PC7-Pad39)") (class "Default")
      (node (ref "U1") (pin "39") (pinfunction "PC7_39") (pintype "bidirectional"))
    )
    (net (code "78") (name "unconnected-(U1A-PC8-Pad40)") (class "Default")
      (node (ref "U1") (pin "40") (pinfunction "PC8_40") (pintype "bidirectional"))
    )
    (net (code "79") (name "unconnected-(U1A-PC9-Pad41)") (class "Default")
      (node (ref "U1") (pin "41") (pinfunction "PC9_41") (pintype "bidirectional"))
    )
    (net (code "80") (name "unconnected-(U1A-PC10-Pad52)") (class "Default")
      (node (ref "U1") (pin "52") (pinfunction "PC10_52") (pintype "bidirectional"))
    )
    (net (code "81") (name "unconnected-(U1A-PC11-Pad53)") (class "Default")
      (node (ref "U1") (pin "53") (pinfunction "PC11_53") (pintype "bidirectional"))
    )
    (net (code "82") (name "unconnected-(U1A-PC12-Pad54)") (class "Default")
      (node (ref "U1") (pin "54") (pinfunction "PC12_54") (pintype "bidirectional"))
    )
    (net (code "83") (name "unconnected-(U1A-PC13-Pad2)") (class "Default")
      (node (ref "U1") (pin "2") (pinfunction "PC13_2") (pintype "bidirectional"))
    )
    (net (code "84") (name "unconnected-(U1A-PC14-OSC32_IN-Pad3)") (class "Default")
      (node (ref "U1") (pin "3") (pinfunction "PC14-OSC32_IN_3") (pintype "bidirectional"))
    )
    (net (code "85") (name "unconnected-(U1A-PC15-OSC32_OUT-Pad4)") (class "Default")
      (node (ref "U1") (pin "4") (pinfunction "PC15-OSC32_OUT_4") (pintype "bidirectional"))
    )
    (net (code "86") (name "unconnected-(U1A-PD2-Pad55)") (class "Default")
      (node (ref "U1") (pin "55") (pinfunction "PD2_55") (pintype "bidirectional"))
    )
  )
)
